# WIFI.net
KiCad netlist of a schematic drawn in Altium Designer
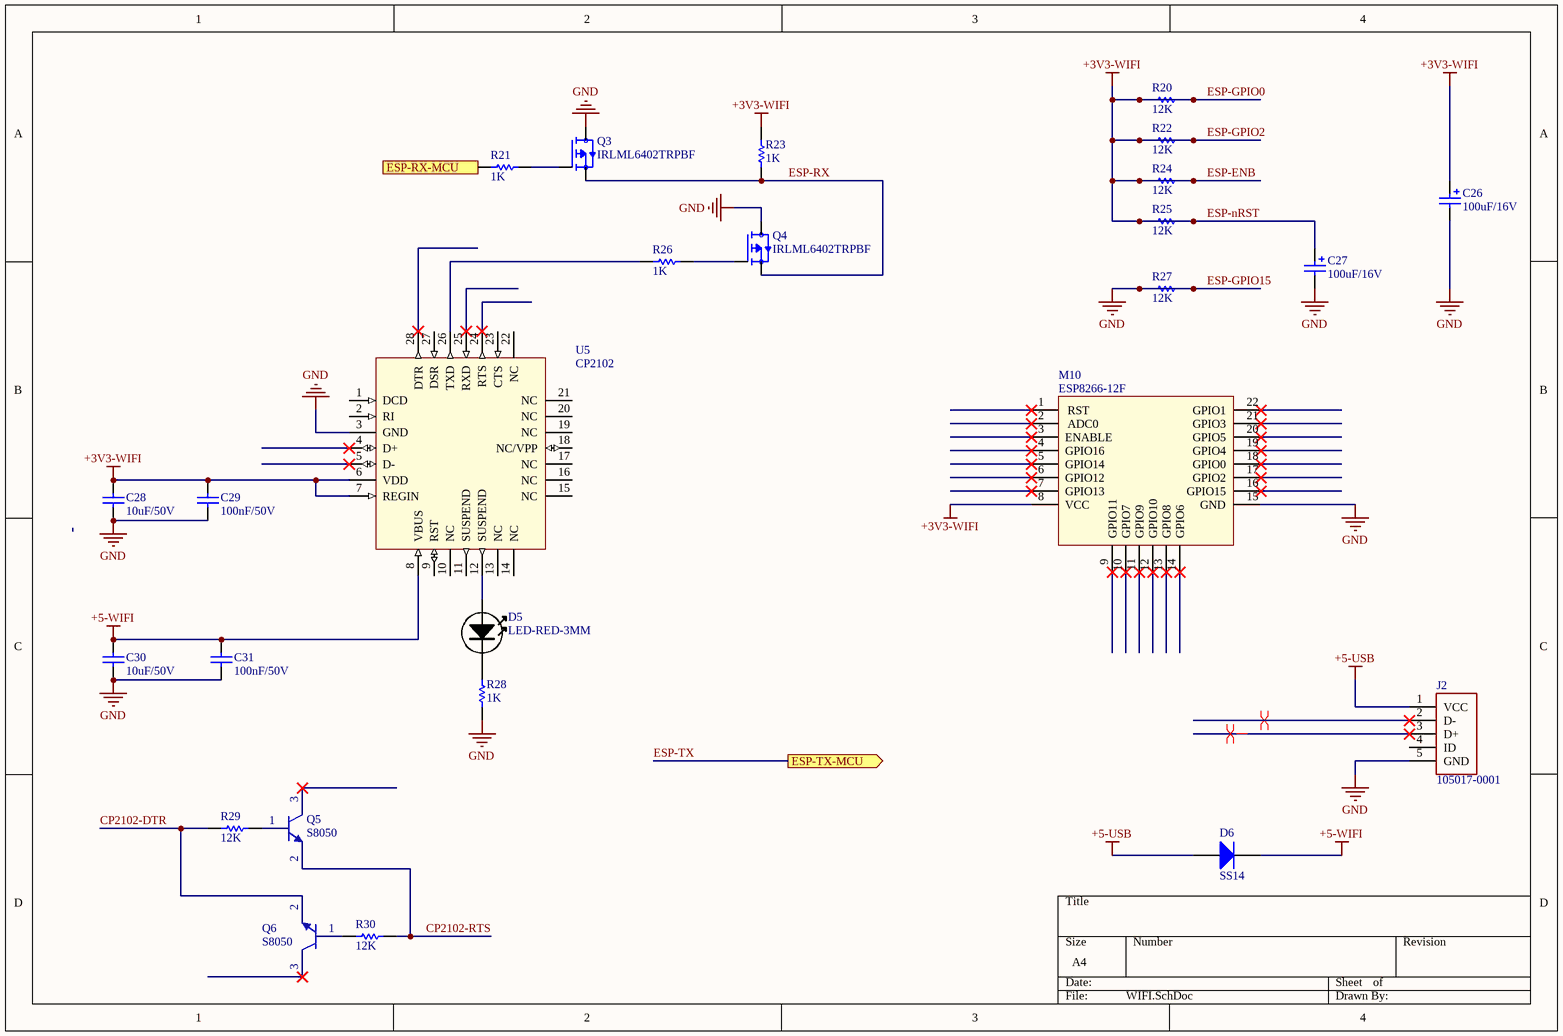
[diagram p0: WIFI.SchDoc]

(export (version "E")
  (design (tool "Eeschema 10.0.6"))
  (components
    (comp (ref "C26")
      (value "100uF/16V")
      (footprint "CAP_SM_TAN")
      (fields
        (field (name "MANUFACTURER") "Nichicon")
        (field (name "MANUFACTURER PART NUMBER") "UWX1C101MCL1GB")
        (field (name "Comment") "TAJB107M006RNJ")
      )
      (libsource (lib "Capacitor") (part "Cap-Tan-100uF-16V"))
    )
    (comp (ref "C27")
      (value "100uF/16V")
      (footprint "CAP_SM_TAN")
      (fields
        (field (name "MANUFACTURER") "Nichicon")
        (field (name "MANUFACTURER PART NUMBER") "UWX1C101MCL1GB")
        (field (name "Comment") "TAJB107M006RNJ")
      )
      (libsource (lib "Capacitor") (part "Cap-Tan-100uF-16V"))
    )
    (comp (ref "C28")
      (value "10uF/50V")
      (footprint "CAP-SM-0805")
      (description "CAP CER 10UF 50V X5R 0805")
      (fields
        (field (name "MANUFACTURER") "Yageo")
        (field (name "MANUFACTURER PART NUMBER") "CC0805KKX5R9BB106")
      )
      (libsource (lib "Capacitor") (part "Cap-10uF-50V-0805"))
    )
    (comp (ref "C29")
      (value "100nF/50V")
      (footprint "CAP-SM-0805")
      (description "CAP CER 0.1UF 50V Y5V 0805")
      (fields
        (field (name "MANUFACTURER") "Samsung Electro-Mechanics")
        (field (name "MANUFACTURER PART NUMBER") "CL21F104ZBCNNNC")
      )
      (libsource (lib "Capacitor") (part "Cap-100nF-50V-0805"))
    )
    (comp (ref "C30")
      (value "10uF/50V")
      (footprint "CAP-SM-0805")
      (description "CAP CER 10UF 50V X5R 0805")
      (fields
        (field (name "MANUFACTURER") "Yageo")
        (field (name "MANUFACTURER PART NUMBER") "CC0805KKX5R9BB106")
      )
      (libsource (lib "Capacitor") (part "Cap-10uF-50V-0805"))
    )
    (comp (ref "C31")
      (value "100nF/50V")
      (footprint "CAP-SM-0805")
      (description "CAP CER 0.1UF 50V Y5V 0805")
      (fields
        (field (name "MANUFACTURER") "Samsung Electro-Mechanics")
        (field (name "MANUFACTURER PART NUMBER") "CL21F104ZBCNNNC")
      )
      (libsource (lib "Capacitor") (part "Cap-100nF-50V-0805"))
    )
    (comp (ref "D5")
      (value "LED-RED-3MM")
      (footprint "LED-3MM-RED")
      (libsource (lib "vh_altium_library") (part "LED-RED-3MM"))
    )
    (comp (ref "D6")
      (value "SS14")
      (footprint "SS14")
      (description "DIODE SCHOTTKY 40V 1A SMA")
      (fields (field (name "MANUFACTURER") "ON Semiconductor"))
      (libsource (lib "Diode") (part "Diode-SS14"))
    )
    (comp (ref "J2")
      (value "105017-0001")
      (footprint "CONN_105017-0001")
      (description "No Description Available")
      (fields (field (name "COPYRIGHT") "Copyright (C) 2018 Accelerated Designs. All rights reserved"))
      (libsource (lib "Header-connector") (part "105017-0001"))
    )
    (comp (ref "M10") (value "ESP8266-12F") (libsource (lib "MyLibrary1") (part "ESP8266-12F")))
    (comp (ref "Q3")
      (value "IRLML6402TRPBF")
      (footprint "SOT95P237X112-3N")
      (fields (field (name "MF") "Infineon"))
      (libsource (lib "IRLML6402TRPBF") (part "IRLML6402TRPBF"))
    )
    (comp (ref "Q4")
      (value "IRLML6402TRPBF")
      (footprint "SOT95P237X112-3N")
      (fields (field (name "MF") "Infineon"))
      (libsource (lib "IRLML6402TRPBF") (part "IRLML6402TRPBF"))
    )
    (comp (ref "Q5") (value "S8050") (footprint "SOT23_NEX") (libsource (lib "BJT") (part "S8050")))
    (comp (ref "Q6") (value "S8050") (footprint "SOT23_NEX") (libsource (lib "BJT") (part "S8050")))
    (comp (ref "R20")
      (value "12K")
      (footprint "Resistor:RES-SM-0805")
      (description "RES 12 KOHM JUMPER 0805")
      (fields
        (field (name "MANUFACTURER") "Vishay Thin Film")
        (field (name "MANUFACTURER PART NUMBER") "PAT0805E3121BST1")
      )
      (libsource (lib "Resistor") (part "Res-12K-0805"))
    )
    (comp (ref "R21")
      (value "1K")
      (footprint "Resistor:RES-SM-0805")
      (description "RES 1K OHM 1% 1/4W 0805")
      (fields
        (field (name "MANUFACTURER") "Stackpole Electronics Inc")
        (field (name "MANUFACTURER PART NUMBER") "RNCP0805FTD1K00")
      )
      (libsource (lib "Resistor") (part "Res-1K-0805"))
    )
    (comp (ref "R22")
      (value "12K")
      (footprint "Resistor:RES-SM-0805")
      (description "RES 12 KOHM JUMPER 0805")
      (fields
        (field (name "MANUFACTURER") "Vishay Thin Film")
        (field (name "MANUFACTURER PART NUMBER") "PAT0805E3121BST1")
      )
      (libsource (lib "Resistor") (part "Res-12K-0805"))
    )
    (comp (ref "R23")
      (value "1K")
      (footprint "Resistor:RES-SM-0805")
      (description "RES 1K OHM 1% 1/4W 0805")
      (fields
        (field (name "MANUFACTURER") "Stackpole Electronics Inc")
        (field (name "MANUFACTURER PART NUMBER") "RNCP0805FTD1K00")
      )
      (libsource (lib "Resistor") (part "Res-1K-0805"))
    )
    (comp (ref "R24")
      (value "12K")
      (footprint "Resistor:RES-SM-0805")
      (description "RES 12 KOHM JUMPER 0805")
      (fields
        (field (name "MANUFACTURER") "Vishay Thin Film")
        (field (name "MANUFACTURER PART NUMBER") "PAT0805E3121BST1")
      )
      (libsource (lib "Resistor") (part "Res-12K-0805"))
    )
    (comp (ref "R25")
      (value "12K")
      (footprint "Resistor:RES-SM-0805")
      (description "RES 12 KOHM JUMPER 0805")
      (fields
        (field (name "MANUFACTURER") "Vishay Thin Film")
        (field (name "MANUFACTURER PART NUMBER") "PAT0805E3121BST1")
      )
      (libsource (lib "Resistor") (part "Res-12K-0805"))
    )
    (comp (ref "R26")
      (value "1K")
      (footprint "Resistor:RES-SM-0805")
      (description "RES 1K OHM 1% 1/4W 0805")
      (fields
        (field (name "MANUFACTURER") "Stackpole Electronics Inc")
        (field (name "MANUFACTURER PART NUMBER") "RNCP0805FTD1K00")
      )
      (libsource (lib "Resistor") (part "Res-1K-0805"))
    )
    (comp (ref "R27")
      (value "12K")
      (footprint "Resistor:RES-SM-0805")
      (description "RES 12 KOHM JUMPER 0805")
      (fields
        (field (name "MANUFACTURER") "Vishay Thin Film")
        (field (name "MANUFACTURER PART NUMBER") "PAT0805E3121BST1")
      )
      (libsource (lib "Resistor") (part "Res-12K-0805"))
    )
    (comp (ref "R28")
      (value "1K")
      (footprint "Resistor:RES-SM-0805")
      (description "RES 1K OHM 1% 1/4W 0805")
      (fields
        (field (name "MANUFACTURER") "Stackpole Electronics Inc")
        (field (name "MANUFACTURER PART NUMBER") "RNCP0805FTD1K00")
      )
      (libsource (lib "Resistor") (part "Res-1K-0805"))
    )
    (comp (ref "R29")
      (value "12K")
      (footprint "Resistor:RES-SM-0805")
      (description "RES 12 KOHM JUMPER 0805")
      (fields
        (field (name "MANUFACTURER") "Vishay Thin Film")
        (field (name "MANUFACTURER PART NUMBER") "PAT0805E3121BST1")
      )
      (libsource (lib "Resistor") (part "Res-12K-0805"))
    )
    (comp (ref "R30")
      (value "12K")
      (footprint "Resistor:RES-SM-0805")
      (description "RES 12 KOHM JUMPER 0805")
      (fields
        (field (name "MANUFACTURER") "Vishay Thin Film")
        (field (name "MANUFACTURER PART NUMBER") "PAT0805E3121BST1")
      )
      (libsource (lib "Resistor") (part "Res-12K-0805"))
    )
    (comp (ref "U5") (value "CP2102") (footprint "CP2102") (libsource (lib "MyLibrary1") (part "CP2102")))
  )
  (nets
    (net (code "1") (name "+3V3-WIFI") (class "Default")
      (node (ref "C26") (pin "1") (pinfunction "1_1") (pintype "passive"))
      (node (ref "C27") (pin "1") (pinfunction "1_1") (pintype "passive"))
      (node (ref "C28") (pin "2") (pinfunction "2_2") (pintype "passive"))
      (node (ref "C29") (pin "2") (pinfunction "2_2") (pintype "passive"))
      (node (ref "M10") (pin "8") (pinfunction "VCC_8") (pintype "passive"))
      (node (ref "R20") (pin "1") (pinfunction "1_1") (pintype "passive"))
      (node (ref "R20") (pin "2") (pinfunction "2_2") (pintype "passive"))
      (node (ref "R22") (pin "1") (pinfunction "1_1") (pintype "passive"))
      (node (ref "R22") (pin "2") (pinfunction "2_2") (pintype "passive"))
      (node (ref "R23") (pin "2") (pinfunction "2_2") (pintype "passive"))
      (node (ref "R24") (pin "1") (pinfunction "1_1") (pintype "passive"))
      (node (ref "R24") (pin "2") (pinfunction "2_2") (pintype "passive"))
      (node (ref "R25") (pin "1") (pinfunction "1_1") (pintype "passive"))
      (node (ref "R25") (pin "2") (pinfunction "2_2") (pintype "passive"))
      (node (ref "U5") (pin "6") (pinfunction "VDD_6") (pintype "passive"))
      (node (ref "U5") (pin "7") (pinfunction "REGIN_7") (pintype "input"))
    )
    (net (code "2") (name "+5-USB") (class "Default")
      (node (ref "D6") (pin "2") (pinfunction "A_2") (pintype "passive"))
      (node (ref "J2") (pin "1") (pinfunction "VCC_1") (pintype "passive"))
    )
    (net (code "3") (name "+5-WIFI") (class "Default")
      (node (ref "C30") (pin "2") (pinfunction "2_2") (pintype "passive"))
      (node (ref "C31") (pin "2") (pinfunction "2_2") (pintype "passive"))
      (node (ref "D6") (pin "1") (pinfunction "K_1") (pintype "passive"))
      (node (ref "U5") (pin "8") (pinfunction "VBUS_8") (pintype "input"))
    )
    (net (code "4") (name "/CP2102-DTR") (class "Default")
      (node (ref "Q6") (pin "2") (pinfunction "E_2") (pintype "passive"))
      (node (ref "R29") (pin "1") (pinfunction "1_1") (pintype "passive"))
    )
    (net (code "5") (name "/CP2102-RTS") (class "Default")
      (node (ref "Q5") (pin "2") (pinfunction "E_2") (pintype "passive"))
      (node (ref "R30") (pin "2") (pinfunction "2_2") (pintype "passive"))
    )
    (net (code "6") (name "/ESP-RX") (class "Default")
      (node (ref "Q3") (pin "2") (pinfunction "S_2") (pintype "passive"))
      (node (ref "Q4") (pin "2") (pinfunction "S_2") (pintype "passive"))
      (node (ref "R23") (pin "1") (pinfunction "1_1") (pintype "passive"))
    )
    (net (code "7") (name "/ESP-RX-MCU") (class "Default")
      (node (ref "R21") (pin "1") (pinfunction "1_1") (pintype "passive"))
    )
    (net (code "9") (name "GND") (class "Default")
      (node (ref "C26") (pin "2") (pinfunction "2_2") (pintype "passive"))
      (node (ref "C27") (pin "2") (pinfunction "2_2") (pintype "passive"))
      (node (ref "C28") (pin "1") (pinfunction "1_1") (pintype "passive"))
      (node (ref "C29") (pin "1") (pinfunction "1_1") (pintype "passive"))
      (node (ref "C30") (pin "1") (pinfunction "1_1") (pintype "passive"))
      (node (ref "C31") (pin "1") (pinfunction "1_1") (pintype "passive"))
      (node (ref "J2") (pin "5") (pinfunction "GND_5") (pintype "passive"))
      (node (ref "M10") (pin "15") (pinfunction "GND_15") (pintype "passive"))
      (node (ref "Q3") (pin "3") (pinfunction "D_3") (pintype "passive"))
      (node (ref "Q4") (pin "3") (pinfunction "D_3") (pintype "passive"))
      (node (ref "R27") (pin "1") (pinfunction "1_1") (pintype "passive"))
      (node (ref "R27") (pin "2") (pinfunction "2_2") (pintype "passive"))
      (node (ref "R28") (pin "1") (pinfunction "1_1") (pintype "passive"))
      (node (ref "U5") (pin "3") (pinfunction "GND_3") (pintype "passive"))
    )
    (net (code "10") (name "Net-(D5-PadA)") (class "Default")
      (node (ref "D5") (pin "A") (pintype "passive"))
      (node (ref "U5") (pin "12") (pinfunction "SUSPEND_12") (pintype "output"))
    )
    (net (code "11") (name "Net-(D5-PadK)") (class "Default")
      (node (ref "D5") (pin "K") (pintype "passive"))
      (node (ref "R28") (pin "2") (pinfunction "2_2") (pintype "passive"))
    )
    (net (code "12") (name "Net-(Q3-G)") (class "Default")
      (node (ref "Q3") (pin "1") (pinfunction "G_1") (pintype "passive"))
      (node (ref "R21") (pin "2") (pinfunction "2_2") (pintype "passive"))
    )
    (net (code "13") (name "Net-(Q4-G)") (class "Default")
      (node (ref "Q4") (pin "1") (pinfunction "G_1") (pintype "passive"))
      (node (ref "R26") (pin "2") (pinfunction "2_2") (pintype "passive"))
    )
    (net (code "14") (name "Net-(Q5-B)") (class "Default")
      (node (ref "Q5") (pin "1") (pinfunction "B_1") (pintype "passive"))
      (node (ref "R29") (pin "2") (pinfunction "2_2") (pintype "passive"))
    )
    (net (code "15") (name "Net-(Q6-B)") (class "Default")
      (node (ref "Q6") (pin "1") (pinfunction "B_1") (pintype "passive"))
      (node (ref "R30") (pin "1") (pinfunction "1_1") (pintype "passive"))
    )
    (net (code "16") (name "Net-(U5-TXD)") (class "Default")
      (node (ref "R26") (pin "1") (pinfunction "1_1") (pintype "passive"))
      (node (ref "U5") (pin "26") (pinfunction "TXD_26") (pintype "output"))
    )
    (net (code "17") (name "unconnected-(J2-D+-Pad3)") (class "Default")
      (node (ref "J2") (pin "3") (pinfunction "D+_3") (pintype "passive+no_connect"))
    )
    (net (code "18") (name "unconnected-(J2-D--Pad2)") (class "Default")
      (node (ref "J2") (pin "2") (pinfunction "D-_2") (pintype "passive+no_connect"))
    )
    (net (code "19") (name "unconnected-(J2-ID-Pad4)") (class "Default")
      (node (ref "J2") (pin "4") (pinfunction "ID_4") (pintype "passive"))
    )
    (net (code "20") (name "unconnected-(M10-ADC0-Pad2)") (class "Default")
      (node (ref "M10") (pin "2") (pinfunction "ADC0_2") (pintype "passive+no_connect"))
    )
    (net (code "21") (name "unconnected-(M10-ENABLE-Pad3)") (class "Default")
      (node (ref "M10") (pin "3") (pinfunction "ENABLE_3") (pintype "passive+no_connect"))
    )
    (net (code "22") (name "unconnected-(M10-GPIO0-Pad18)") (class "Default")
      (node (ref "M10") (pin "18") (pinfunction "GPIO0_18") (pintype "passive+no_connect"))
    )
    (net (code "23") (name "unconnected-(M10-GPIO1-Pad22)") (class "Default")
      (node (ref "M10") (pin "22") (pinfunction "GPIO1_22") (pintype "passive+no_connect"))
    )
    (net (code "24") (name "unconnected-(M10-GPIO2-Pad17)") (class "Default")
      (node (ref "M10") (pin "17") (pinfunction "GPIO2_17") (pintype "passive+no_connect"))
    )
    (net (code "25") (name "unconnected-(M10-GPIO3-Pad21)") (class "Default")
      (node (ref "M10") (pin "21") (pinfunction "GPIO3_21") (pintype "passive+no_connect"))
    )
    (net (code "26") (name "unconnected-(M10-GPIO4-Pad19)") (class "Default")
      (node (ref "M10") (pin "19") (pinfunction "GPIO4_19") (pintype "passive+no_connect"))
    )
    (net (code "27") (name "unconnected-(M10-GPIO5-Pad20)") (class "Default")
      (node (ref "M10") (pin "20") (pinfunction "GPIO5_20") (pintype "passive+no_connect"))
    )
    (net (code "28") (name "unconnected-(M10-GPIO6-Pad14)") (class "Default")
      (node (ref "M10") (pin "14") (pinfunction "GPIO6_14") (pintype "passive+no_connect"))
    )
    (net (code "29") (name "unconnected-(M10-GPIO7-Pad10)") (class "Default")
      (node (ref "M10") (pin "10") (pinfunction "GPIO7_10") (pintype "passive+no_connect"))
    )
    (net (code "30") (name "unconnected-(M10-GPIO8-Pad13)") (class "Default")
      (node (ref "M10") (pin "13") (pinfunction "GPIO8_13") (pintype "passive+no_connect"))
    )
    (net (code "31") (name "unconnected-(M10-GPIO9-Pad11)") (class "Default")
      (node (ref "M10") (pin "11") (pinfunction "GPIO9_11") (pintype "passive+no_connect"))
    )
    (net (code "32") (name "unconnected-(M10-GPIO10-Pad12)") (class "Default")
      (node (ref "M10") (pin "12") (pinfunction "GPIO10_12") (pintype "passive+no_connect"))
    )
    (net (code "33") (name "unconnected-(M10-GPIO11-Pad9)") (class "Default")
      (node (ref "M10") (pin "9") (pinfunction "GPIO11_9") (pintype "passive+no_connect"))
    )
    (net (code "34") (name "unconnected-(M10-GPIO12-Pad6)") (class "Default")
      (node (ref "M10") (pin "6") (pinfunction "GPIO12_6") (pintype "passive+no_connect"))
    )
    (net (code "35") (name "unconnected-(M10-GPIO13-Pad7)") (class "Default")
      (node (ref "M10") (pin "7") (pinfunction "GPIO13_7") (pintype "passive+no_connect"))
    )
    (net (code "36") (name "unconnected-(M10-GPIO14-Pad5)") (class "Default")
      (node (ref "M10") (pin "5") (pinfunction "GPIO14_5") (pintype "passive+no_connect"))
    )
    (net (code "37") (name "unconnected-(M10-GPIO15-Pad16)") (class "Default")
      (node (ref "M10") (pin "16") (pinfunction "GPIO15_16") (pintype "passive+no_connect"))
    )
    (net (code "38") (name "unconnected-(M10-GPIO16-Pad4)") (class "Default")
      (node (ref "M10") (pin "4") (pinfunction "GPIO16_4") (pintype "passive+no_connect"))
    )
    (net (code "39") (name "unconnected-(M10-RST-Pad1)") (class "Default")
      (node (ref "M10") (pin "1") (pinfunction "RST_1") (pintype "passive+no_connect"))
    )
    (net (code "40") (name "unconnected-(Q5-C-Pad3)") (class "Default")
      (node (ref "Q5") (pin "3") (pinfunction "C_3") (pintype "passive+no_connect"))
    )
    (net (code "41") (name "unconnected-(Q6-C-Pad3)") (class "Default")
      (node (ref "Q6") (pin "3") (pinfunction "C_3") (pintype "passive+no_connect"))
    )
    (net (code "42") (name "unconnected-(U5-CTS-Pad23)") (class "Default")
      (node (ref "U5") (pin "23") (pinfunction "CTS_23") (pintype "input"))
    )
    (net (code "43") (name "unconnected-(U5-D+-Pad4)") (class "Default")
      (node (ref "U5") (pin "4") (pinfunction "D+_4") (pintype "bidirectional+no_connect"))
    )
    (net (code "44") (name "unconnected-(U5-D--Pad5)") (class "Default")
      (node (ref "U5") (pin "5") (pinfunction "D-_5") (pintype "bidirectional+no_connect"))
    )
    (net (code "45") (name "unconnected-(U5-DCD-Pad1)") (class "Default")
      (node (ref "U5") (pin "1") (pinfunction "DCD_1") (pintype "input"))
    )
    (net (code "46") (name "unconnected-(U5-DSR-Pad27)") (class "Default")
      (node (ref "U5") (pin "27") (pinfunction "DSR_27") (pintype "input"))
    )
    (net (code "47") (name "unconnected-(U5-DTR-Pad28)") (class "Default")
      (node (ref "U5") (pin "28") (pinfunction "DTR_28") (pintype "output+no_connect"))
    )
    (net (code "48") (name "unconnected-(U5-NC-Pad10)") (class "Default")
      (node (ref "U5") (pin "10") (pinfunction "NC_10") (pintype "passive"))
    )
    (net (code "49") (name "unconnected-(U5-NC-Pad13)") (class "Default")
      (node (ref "U5") (pin "13") (pinfunction "NC_13") (pintype "passive"))
    )
    (net (code "50") (name "unconnected-(U5-NC-Pad14)") (class "Default")
      (node (ref "U5") (pin "14") (pinfunction "NC_14") (pintype "passive"))
    )
    (net (code "51") (name "unconnected-(U5-NC-Pad15)") (class "Default")
      (node (ref "U5") (pin "15") (pinfunction "NC_15") (pintype "passive"))
    )
    (net (code "52") (name "unconnected-(U5-NC-Pad16)") (class "Default")
      (node (ref "U5") (pin "16") (pinfunction "NC_16") (pintype "passive"))
    )
    (net (code "53") (name "unconnected-(U5-NC-Pad17)") (class "Default")
      (node (ref "U5") (pin "17") (pinfunction "NC_17") (pintype "passive"))
    )
    (net (code "54") (name "unconnected-(U5-NC-Pad19)") (class "Default")
      (node (ref "U5") (pin "19") (pinfunction "NC_19") (pintype "passive"))
    )
    (net (code "55") (name "unconnected-(U5-NC-Pad20)") (class "Default")
      (node (ref "U5") (pin "20") (pinfunction "NC_20") (pintype "passive"))
    )
    (net (code "56") (name "unconnected-(U5-NC-Pad21)") (class "Default")
      (node (ref "U5") (pin "21") (pinfunction "NC_21") (pintype "passive"))
    )
    (net (code "57") (name "unconnected-(U5-NC-Pad22)") (class "Default")
      (node (ref "U5") (pin "22") (pinfunction "NC_22") (pintype "passive"))
    )
    (net (code "58") (name "unconnected-(U5-NC{slash}VPP-Pad18)") (class "Default")
      (node (ref "U5") (pin "18") (pinfunction "NC/VPP_18") (pintype "bidirectional"))
    )
    (net (code "59") (name "unconnected-(U5-RI-Pad2)") (class "Default")
      (node (ref "U5") (pin "2") (pinfunction "RI_2") (pintype "input"))
    )
    (net (code "60") (name "unconnected-(U5-RST-Pad9)") (class "Default")
      (node (ref "U5") (pin "9") (pinfunction "RST_9") (pintype "bidirectional"))
    )
    (net (code "61") (name "unconnected-(U5-RTS-Pad24)") (class "Default")
      (node (ref "U5") (pin "24") (pinfunction "RTS_24") (pintype "output+no_connect"))
    )
    (net (code "62") (name "unconnected-(U5-RXD-Pad25)") (class "Default")
      (node (ref "U5") (pin "25") (pinfunction "RXD_25") (pintype "input+no_connect"))
    )
    (net (code "63") (name "unconnected-(U5-SUSPEND-Pad11)") (class "Default")
      (node (ref "U5") (pin "11") (pinfunction "SUSPEND_11") (pintype "output"))
    )
  )
)
